# Sheet_1_2023-02-27.net
KiCad netlist of a schematic drawn in Altium Designer
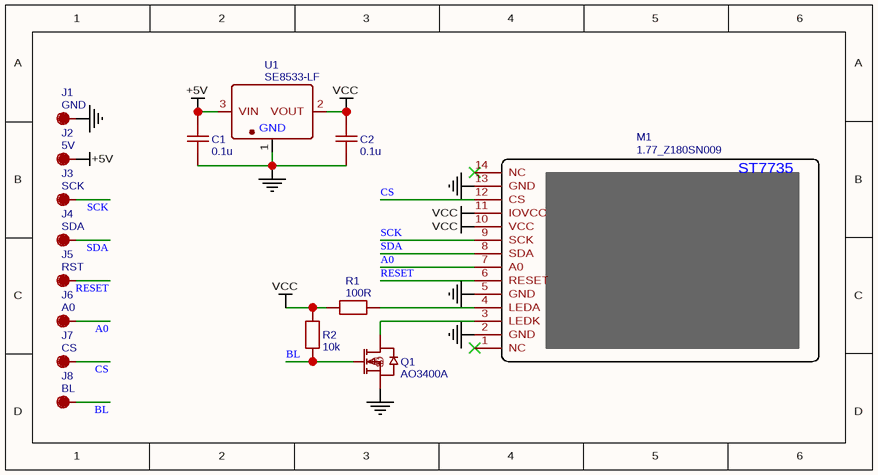
[diagram p0: Sheet_1_2023-02-27.schdoc]

(export (version "E")
  (design (tool "Eeschema 10.0.6"))
  (components
    (comp (ref "C1")
      (value "0.1u")
      (fields (field (name "CONTRIBUTOR") "LCEDA_Lib"))
      (libsource (lib "altium-import") (part "root_1_0.1u_"))
    )
    (comp (ref "C2")
      (value "0.1u")
      (fields (field (name "CONTRIBUTOR") "LCEDA_Lib"))
      (libsource (lib "altium-import") (part "root_1_0.1u_"))
    )
    (comp (ref "J1")
      (value "GND")
      (fields (field (name "CONTRIBUTOR") "私有工程"))
      (libsource (lib "altium-import") (part "root_0_GND_"))
    )
    (comp (ref "J2")
      (value "5V")
      (fields (field (name "CONTRIBUTOR") "私有工程"))
      (libsource (lib "altium-import") (part "root_0_5V_"))
    )
    (comp (ref "J3")
      (value "SCK")
      (fields (field (name "CONTRIBUTOR") "私有工程"))
      (libsource (lib "altium-import") (part "root_0_SCK_"))
    )
    (comp (ref "J4")
      (value "SDA")
      (fields (field (name "CONTRIBUTOR") "私有工程"))
      (libsource (lib "altium-import") (part "root_0_SDA_"))
    )
    (comp (ref "J5")
      (value "RST")
      (fields (field (name "CONTRIBUTOR") "私有工程"))
      (libsource (lib "altium-import") (part "root_0_RST_"))
    )
    (comp (ref "J6")
      (value "A0")
      (fields (field (name "CONTRIBUTOR") "私有工程"))
      (libsource (lib "altium-import") (part "root_0_A0_"))
    )
    (comp (ref "J7")
      (value "CS")
      (fields (field (name "CONTRIBUTOR") "私有工程"))
      (libsource (lib "altium-import") (part "root_0_CS_"))
    )
    (comp (ref "J8")
      (value "BL")
      (fields (field (name "CONTRIBUTOR") "私有工程"))
      (libsource (lib "altium-import") (part "root_0_BL_"))
    )
    (comp (ref "M1")
      (value "1.77_Z180SN009")
      (fields (field (name "CONTRIBUTOR") "私有工程"))
      (libsource (lib "altium-import") (part "root_0_1.77_Z180SN009_"))
    )
    (comp (ref "Q1")
      (value "AO3400A")
      (fields (field (name "BOM_SUPPLIER PART") "C20917") (field (name "CONTRIBUTOR") "私有工程"))
      (libsource (lib "altium-import") (part "root_0_AO3400A_"))
    )
    (comp (ref "R1")
      (value "100R")
      (fields (field (name "CONTRIBUTOR") "LCEDA_Lib"))
      (libsource (lib "altium-import") (part "root_0_100R_"))
    )
    (comp (ref "R2")
      (value "10k")
      (fields (field (name "CONTRIBUTOR") "LCEDA_Lib"))
      (libsource (lib "altium-import") (part "root_1_10k_"))
    )
    (comp (ref "U1")
      (value "SE8533-LF")
      (fields (field (name "BOM_SUPPLIER PART") "C115016") (field (name "CONTRIBUTOR") "私有工程"))
      (libsource (lib "altium-import") (part "root_0_SE8533-LF_"))
    )
  )
  (nets
    (net (code "1") (name "+5V") (class "Default")
      (node (ref "C1") (pin "2") (pinfunction "2_2") (pintype "passive"))
      (node (ref "J2") (pin "1") (pinfunction "TEST_1") (pintype "passive"))
      (node (ref "U1") (pin "3") (pinfunction "VIN_3") (pintype "passive"))
    )
    (net (code "2") (name "/A0") (class "Default")
      (node (ref "J6") (pin "1") (pinfunction "TEST_1") (pintype "passive"))
      (node (ref "M1") (pin "7") (pinfunction "A0_7") (pintype "passive"))
    )
    (net (code "3") (name "/BL") (class "Default")
      (node (ref "J8") (pin "1") (pinfunction "TEST_1") (pintype "passive"))
      (node (ref "Q1") (pin "1") (pinfunction "G_1") (pintype "passive"))
      (node (ref "R2") (pin "1") (pinfunction "1_1") (pintype "passive"))
    )
    (net (code "4") (name "/CS") (class "Default")
      (node (ref "J7") (pin "1") (pinfunction "TEST_1") (pintype "passive"))
      (node (ref "M1") (pin "12") (pinfunction "CS_12") (pintype "passive"))
    )
    (net (code "5") (name "/RESET") (class "Default")
      (node (ref "J5") (pin "1") (pinfunction "TEST_1") (pintype "passive"))
      (node (ref "M1") (pin "6") (pinfunction "RESET_6") (pintype "passive"))
    )
    (net (code "6") (name "/SCK") (class "Default")
      (node (ref "J3") (pin "1") (pinfunction "TEST_1") (pintype "passive"))
      (node (ref "M1") (pin "9") (pinfunction "SCK_9") (pintype "passive"))
    )
    (net (code "7") (name "/SDA") (class "Default")
      (node (ref "J4") (pin "1") (pinfunction "TEST_1") (pintype "passive"))
      (node (ref "M1") (pin "8") (pinfunction "SDA_8") (pintype "passive"))
    )
    (net (code "8") (name "GND") (class "Default")
      (node (ref "C1") (pin "1") (pinfunction "1_1") (pintype "passive"))
      (node (ref "C2") (pin "1") (pinfunction "1_1") (pintype "passive"))
      (node (ref "J1") (pin "1") (pinfunction "TEST_1") (pintype "passive"))
      (node (ref "M1") (pin "13") (pinfunction "GND_13") (pintype "passive"))
      (node (ref "M1") (pin "2") (pinfunction "GND_2") (pintype "passive"))
      (node (ref "M1") (pin "5") (pinfunction "GND_5") (pintype "passive"))
      (node (ref "Q1") (pin "2") (pinfunction "S_2") (pintype "passive"))
      (node (ref "U1") (pin "1") (pinfunction "GND_1") (pintype "passive"))
    )
    (net (code "9") (name "Net-(M1-LEDA)") (class "Default")
      (node (ref "M1") (pin "4") (pinfunction "LEDA_4") (pintype "passive"))
      (node (ref "R1") (pin "2") (pinfunction "2_2") (pintype "passive"))
    )
    (net (code "10") (name "Net-(M1-LEDK)") (class "Default")
      (node (ref "M1") (pin "3") (pinfunction "LEDK_3") (pintype "passive"))
      (node (ref "Q1") (pin "3") (pinfunction "D_3") (pintype "passive"))
    )
    (net (code "11") (name "VCC") (class "Default")
      (node (ref "C2") (pin "2") (pinfunction "2_2") (pintype "passive"))
      (node (ref "M1") (pin "10") (pinfunction "VCC_10") (pintype "passive"))
      (node (ref "M1") (pin "11") (pinfunction "IOVCC_11") (pintype "passive"))
      (node (ref "R1") (pin "1") (pinfunction "1_1") (pintype "passive"))
      (node (ref "R2") (pin "2") (pinfunction "2_2") (pintype "passive"))
      (node (ref "U1") (pin "2") (pinfunction "VOUT_2") (pintype "passive"))
    )
    (net (code "12") (name "unconnected-(M1-NC-Pad1)") (class "Default")
      (node (ref "M1") (pin "1") (pinfunction "NC_1") (pintype "passive+no_connect"))
    )
    (net (code "13") (name "unconnected-(M1-NC-Pad14)") (class "Default")
      (node (ref "M1") (pin "14") (pinfunction "NC_14") (pintype "passive+no_connect"))
    )
  )
)
